# connector.net
KiCad netlist of a schematic drawn in Altium Designer
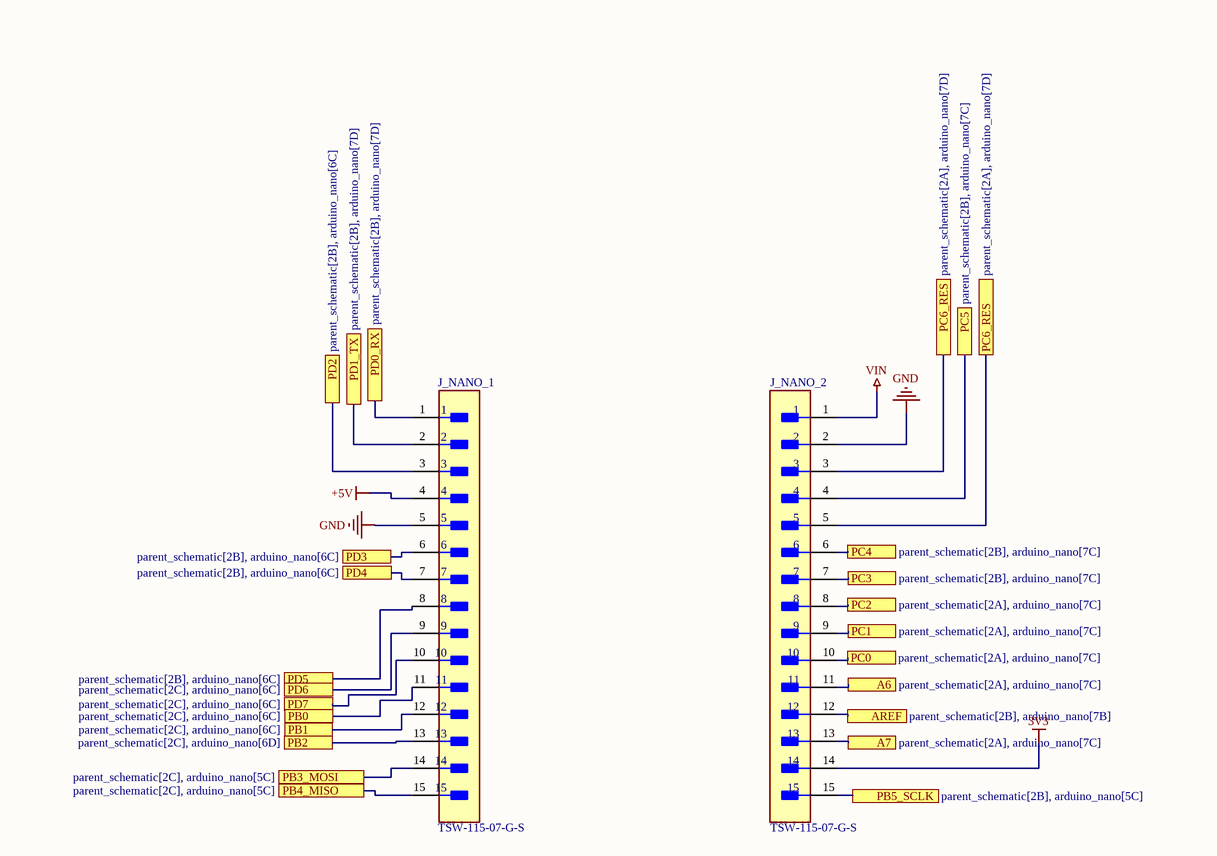
[diagram p0: connector.SchDoc]

(export (version "E")
  (design (tool "Eeschema 10.0.6"))
  (components
    (comp (ref "J_NANO_1")
      (value "TSW-115-07-G-S")
      (footprint "FP-TSW-115-07-G-S-MFG")
      (description "CONN HEADER VERT 15POS 2.54MM")
      (fields
        (field (name "OCTOPART") "https://octopart.com/tsw-115-07-g-s-samtec-272210")
        (field (name "MANUFACTURER") "SAMTEC")
      )
      (libsource (lib "") (part "9e54aee09c46527fb07af492d4d8164_1"))
    )
    (comp (ref "J_NANO_2")
      (value "TSW-115-07-G-S")
      (footprint "FP-TSW-115-07-G-S-MFG")
      (description "CONN HEADER VERT 15POS 2.54MM")
      (fields
        (field (name "OCTOPART") "https://octopart.com/tsw-115-07-g-s-samtec-272210")
        (field (name "MANUFACTURER") "SAMTEC")
      )
      (libsource (lib "Altium Content Vault") (part "9e54aee09c46527fb07af492d4d8164"))
    )
  )
  (nets
    (net (code "1") (name "+5V") (class "Default")
      (node (ref "J_NANO_1") (pin "4") (pinfunction "4_4") (pintype "passive"))
    )
    (net (code "2") (name "/A6") (class "Default")
      (node (ref "J_NANO_2") (pin "11") (pinfunction "11_11") (pintype "passive"))
    )
    (net (code "3") (name "/A7") (class "Default")
      (node (ref "J_NANO_2") (pin "13") (pinfunction "13_13") (pintype "passive"))
    )
    (net (code "4") (name "/AREF") (class "Default")
      (node (ref "J_NANO_2") (pin "12") (pinfunction "12_12") (pintype "passive"))
    )
    (net (code "5") (name "/PB0") (class "Default")
      (node (ref "J_NANO_1") (pin "11") (pinfunction "11_11") (pintype "passive"))
    )
    (net (code "6") (name "/PB1") (class "Default")
      (node (ref "J_NANO_1") (pin "12") (pinfunction "12_12") (pintype "passive"))
    )
    (net (code "7") (name "/PB2") (class "Default")
      (node (ref "J_NANO_1") (pin "13") (pinfunction "13_13") (pintype "passive"))
    )
    (net (code "8") (name "/PB3_MOSI") (class "Default")
      (node (ref "J_NANO_1") (pin "14") (pinfunction "14_14") (pintype "passive"))
    )
    (net (code "9") (name "/PB4_MISO") (class "Default")
      (node (ref "J_NANO_1") (pin "15") (pinfunction "15_15") (pintype "passive"))
    )
    (net (code "10") (name "/PB5_SCLK") (class "Default")
      (node (ref "J_NANO_2") (pin "15") (pinfunction "15_15") (pintype "passive"))
    )
    (net (code "11") (name "/PC0") (class "Default")
      (node (ref "J_NANO_2") (pin "10") (pinfunction "10_10") (pintype "passive"))
    )
    (net (code "12") (name "/PC1") (class "Default")
      (node (ref "J_NANO_2") (pin "9") (pinfunction "9_9") (pintype "passive"))
    )
    (net (code "13") (name "/PC2") (class "Default")
      (node (ref "J_NANO_2") (pin "8") (pinfunction "8_8") (pintype "passive"))
    )
    (net (code "14") (name "/PC3") (class "Default")
      (node (ref "J_NANO_2") (pin "7") (pinfunction "7_7") (pintype "passive"))
    )
    (net (code "15") (name "/PC4") (class "Default")
      (node (ref "J_NANO_2") (pin "6") (pinfunction "6_6") (pintype "passive"))
    )
    (net (code "16") (name "/PC5") (class "Default")
      (node (ref "J_NANO_2") (pin "4") (pinfunction "4_4") (pintype "passive"))
    )
    (net (code "17") (name "/PC6_RES") (class "Default")
      (node (ref "J_NANO_2") (pin "3") (pinfunction "3_3") (pintype "passive"))
      (node (ref "J_NANO_2") (pin "5") (pinfunction "5_5") (pintype "passive"))
    )
    (net (code "18") (name "/PD0_RX") (class "Default")
      (node (ref "J_NANO_1") (pin "1") (pinfunction "1_1") (pintype "passive"))
    )
    (net (code "19") (name "/PD1_TX") (class "Default")
      (node (ref "J_NANO_1") (pin "2") (pinfunction "2_2") (pintype "passive"))
    )
    (net (code "20") (name "/PD2") (class "Default")
      (node (ref "J_NANO_1") (pin "3") (pinfunction "3_3") (pintype "passive"))
    )
    (net (code "21") (name "/PD3") (class "Default")
      (node (ref "J_NANO_1") (pin "6") (pinfunction "6_6") (pintype "passive"))
    )
    (net (code "22") (name "/PD4") (class "Default")
      (node (ref "J_NANO_1") (pin "7") (pinfunction "7_7") (pintype "passive"))
    )
    (net (code "23") (name "/PD5") (class "Default")
      (node (ref "J_NANO_1") (pin "8") (pinfunction "8_8") (pintype "passive"))
    )
    (net (code "24") (name "/PD6") (class "Default")
      (node (ref "J_NANO_1") (pin "9") (pinfunction "9_9") (pintype "passive"))
    )
    (net (code "25") (name "/PD7") (class "Default")
      (node (ref "J_NANO_1") (pin "10") (pinfunction "10_10") (pintype "passive"))
    )
    (net (code "26") (name "3V3") (class "Default")
      (node (ref "J_NANO_2") (pin "14") (pinfunction "14_14") (pintype "passive"))
    )
    (net (code "27") (name "GND") (class "Default")
      (node (ref "J_NANO_1") (pin "5") (pinfunction "5_5") (pintype "passive"))
      (node (ref "J_NANO_2") (pin "2") (pinfunction "2_2") (pintype "passive"))
    )
    (net (code "28") (name "VIN") (class "Default")
      (node (ref "J_NANO_2") (pin "1") (pinfunction "1_1") (pintype "passive"))
    )
  )
)
